# Un_RF.net
KiCad netlist of a schematic drawn in EAGLE
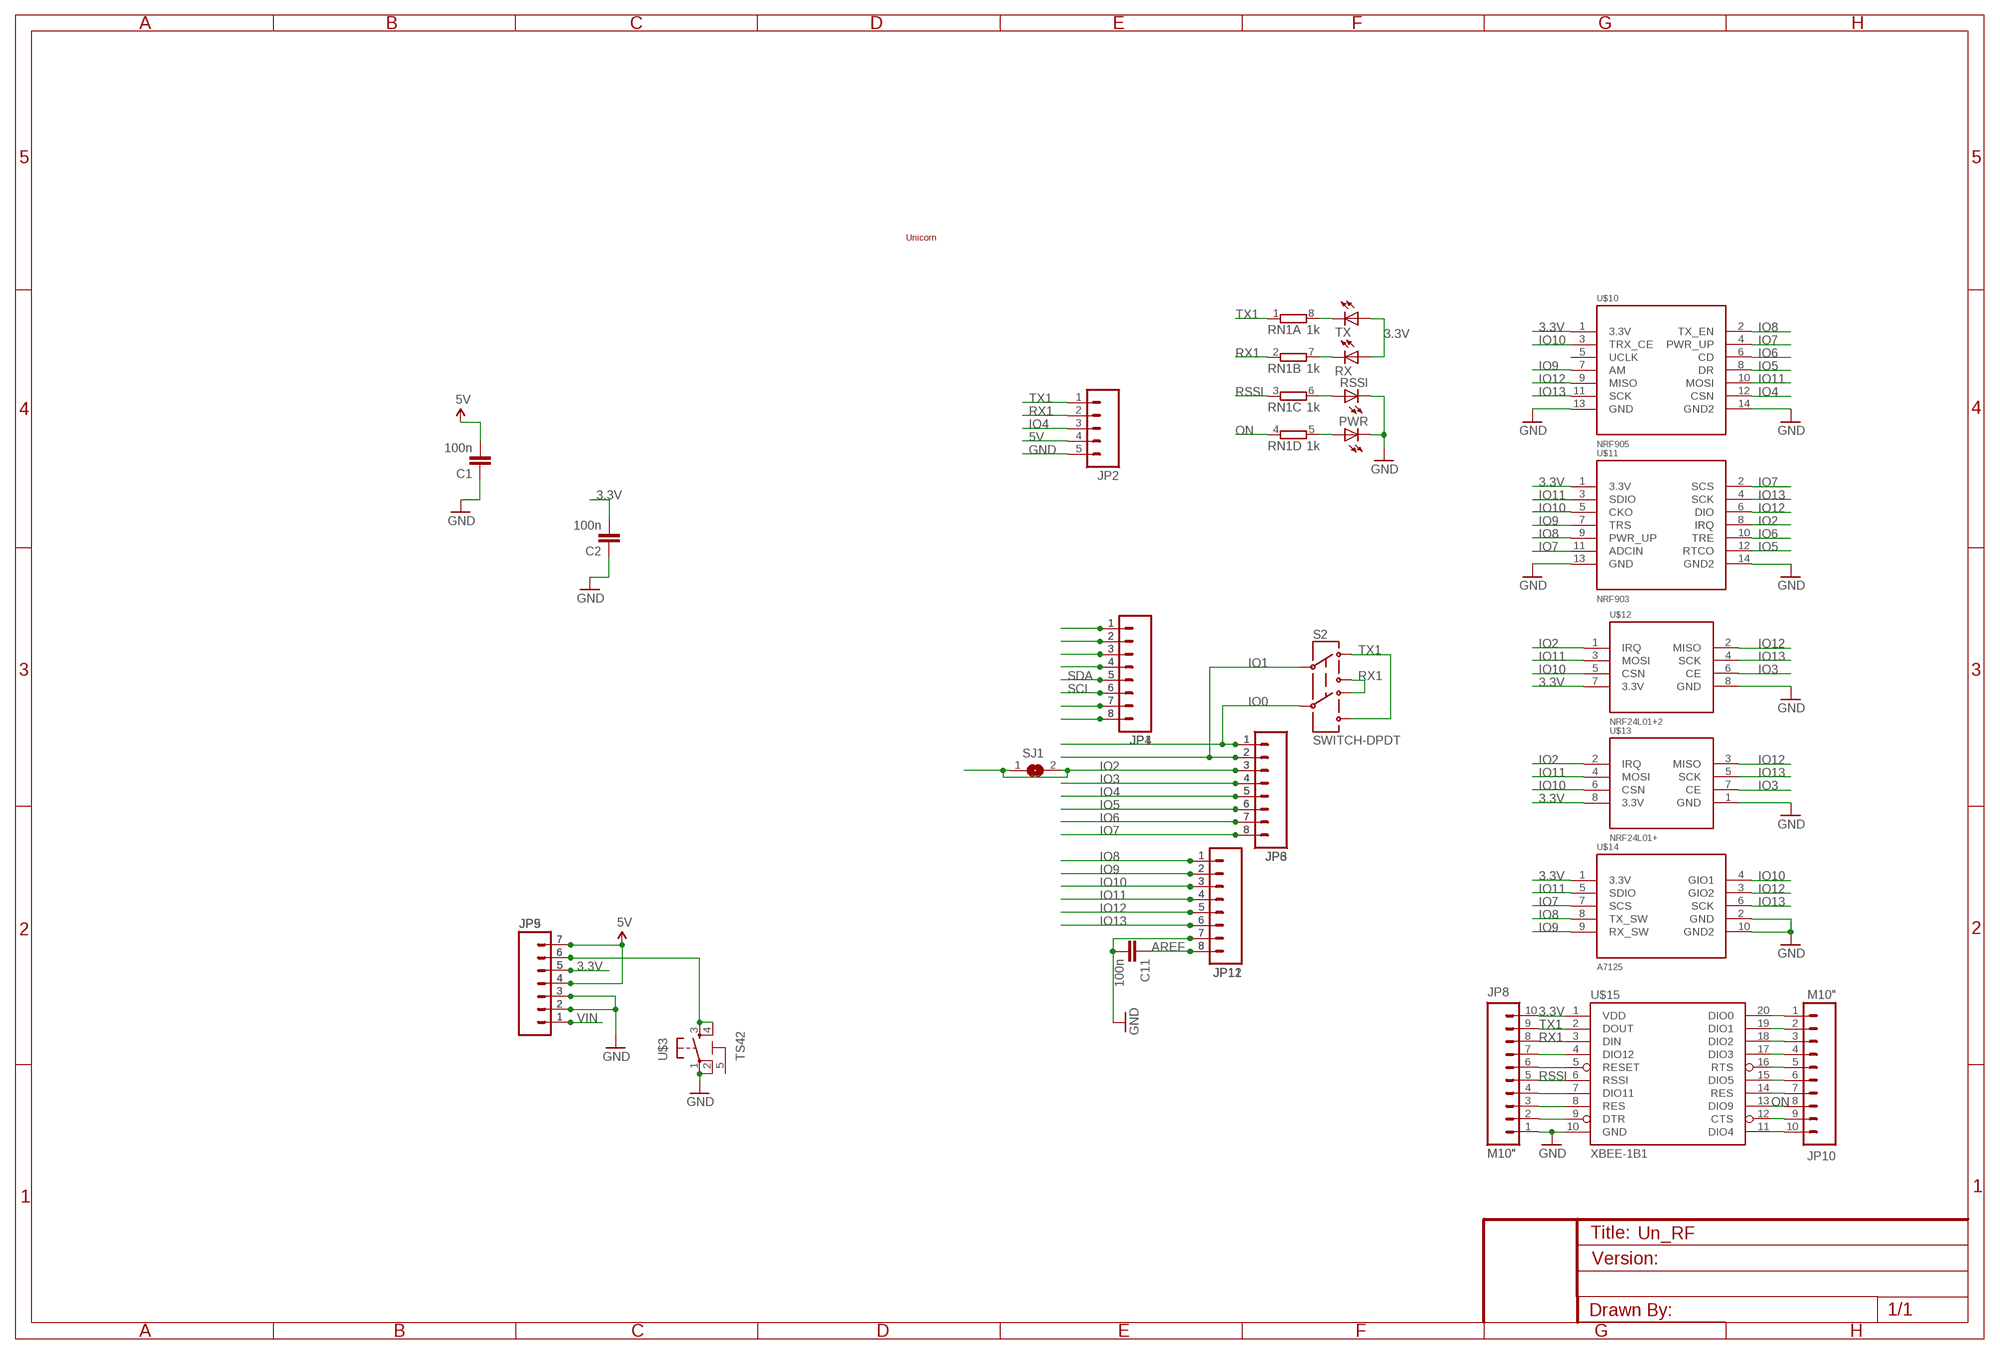
[diagram p0: schematic, sheet 1]

(export (version "E")
  (design (tool "Eeschema 10.0.6"))
  (components
    (comp (ref "C1")
      (value "100n")
      (footprint "eagle-import:0603-CAP")
      (libsource (lib "eagle-import") (part "CAP0603-CAP"))
    )
    (comp (ref "C2")
      (value "100n")
      (footprint "eagle-import:0603-CAP")
      (libsource (lib "eagle-import") (part "CAP0603-CAP"))
    )
    (comp (ref "C11")
      (value "100n")
      (footprint "eagle-import:0603-CAP")
      (libsource (lib "eagle-import") (part "CAP0603-CAP"))
    )
    (comp (ref "JP1")
      (value "M081X08")
      (footprint "eagle-import:1X08")
      (libsource (lib "eagle-import") (part "M081X08"))
    )
    (comp (ref "JP2")
      (value "M05PTH")
      (footprint "eagle-import:1X05")
      (libsource (lib "eagle-import") (part "M05PTH"))
    )
    (comp (ref "JP3")
      (value "M08")
      (footprint "eagle-import:1X08")
      (libsource (lib "eagle-import") (part "M08"))
    )
    (comp (ref "JP4")
      (value "M081X08")
      (footprint "eagle-import:1X08")
      (libsource (lib "eagle-import") (part "M081X08"))
    )
    (comp (ref "JP5")
      (value "M07")
      (footprint "eagle-import:1X07")
      (libsource (lib "eagle-import") (part "M07"))
    )
    (comp (ref "JP6")
      (value "M08")
      (footprint "eagle-import:1X08")
      (libsource (lib "eagle-import") (part "M08"))
    )
    (comp (ref "JP8")
      (value "M10\"")
      (footprint "eagle-import:1X10")
      (libsource (lib "eagle-import") (part "M10{dblquote}"))
    )
    (comp (ref "JP9")
      (value "M07")
      (footprint "eagle-import:1X07")
      (libsource (lib "eagle-import") (part "M07"))
    )
    (comp (ref "JP10")
      (value "M10\"")
      (footprint "eagle-import:1X10")
      (libsource (lib "eagle-import") (part "M10{dblquote}"))
    )
    (comp (ref "JP11")
      (value "M081X08")
      (footprint "eagle-import:1X08")
      (libsource (lib "eagle-import") (part "M081X08"))
    )
    (comp (ref "JP12")
      (value "M081X08")
      (footprint "eagle-import:1X08")
      (libsource (lib "eagle-import") (part "M081X08"))
    )
    (comp (ref "PWR")
      (value "LED0805")
      (footprint "eagle-import:LED-0805")
      (libsource (lib "eagle-import") (part "LED0805"))
    )
    (comp (ref "RN1")
      (value "1k")
      (footprint "eagle-import:CAY16")
      (libsource (lib "eagle-import") (part "4R-NCAY16"))
    )
    (comp (ref "RSSI")
      (value "LED0805")
      (footprint "eagle-import:LED-0805")
      (libsource (lib "eagle-import") (part "LED0805"))
    )
    (comp (ref "RX")
      (value "LED0805")
      (footprint "eagle-import:LED-0805")
      (libsource (lib "eagle-import") (part "LED0805"))
    )
    (comp (ref "S2")
      (value "SWITCH-DPDT")
      (footprint "eagle-import:SWITCH-P2")
      (libsource (lib "eagle-import") (part "SWITCH-DPDT"))
    )
    (comp (ref "SJ1") (value "SJ") (footprint "eagle-import:SJ") (libsource (lib "eagle-import") (part "SJ")))
    (comp (ref "TX")
      (value "LED0805")
      (footprint "eagle-import:LED-0805")
      (libsource (lib "eagle-import") (part "LED0805"))
    )
    (comp (ref "U$3")
      (value "TS42")
      (footprint "eagle-import:TS42")
      (libsource (lib "eagle-import") (part "TS42"))
    )
    (comp (ref "U$4")
      (value "UNICORN")
      (footprint "eagle-import:UNICORN_1")
      (libsource (lib "eagle-import") (part "UNICORN"))
    )
    (comp (ref "U$10")
      (value "NRF905")
      (footprint "eagle-import:2X7")
      (libsource (lib "eagle-import") (part "NRF905"))
    )
    (comp (ref "U$11")
      (value "NRF903")
      (footprint "eagle-import:2X7")
      (libsource (lib "eagle-import") (part "NRF903"))
    )
    (comp (ref "U$12")
      (value "NRF24L01+2")
      (footprint "eagle-import:2X4")
      (libsource (lib "eagle-import") (part "NRF24L01+2"))
    )
    (comp (ref "U$13")
      (value "NRF24L01+")
      (footprint "eagle-import:1X08")
      (libsource (lib "eagle-import") (part "NRF24L01+"))
    )
    (comp (ref "U$14")
      (value "A7125")
      (footprint "eagle-import:1X10-2MM")
      (libsource (lib "eagle-import") (part "A7125"))
    )
    (comp (ref "U$15")
      (value "XBEE-1B1")
      (footprint "eagle-import:XBEE-1")
      (libsource (lib "eagle-import") (part "XBEE-1B1"))
    )
  )
  (nets
    (net (code "1") (name "/3.3V") (class "Default")
      (node (ref "C2") (pin "2") (pinfunction "2_2") (pintype "passive"))
      (node (ref "JP5") (pin "5") (pinfunction "5_5") (pintype "passive"))
      (node (ref "JP8") (pin "10") (pinfunction "10_10") (pintype "passive"))
      (node (ref "JP9") (pin "5") (pinfunction "5_5") (pintype "passive"))
      (node (ref "RX") (pin "1") (pinfunction "A_1") (pintype "passive"))
      (node (ref "TX") (pin "1") (pinfunction "A_1") (pintype "passive"))
      (node (ref "U$10") (pin "1") (pinfunction "3.3V_1") (pintype "bidirectional"))
      (node (ref "U$11") (pin "1") (pinfunction "3.3V_1") (pintype "bidirectional"))
      (node (ref "U$12") (pin "7") (pinfunction "3.3V_7") (pintype "bidirectional"))
      (node (ref "U$13") (pin "8") (pinfunction "3.3V_8") (pintype "bidirectional"))
      (node (ref "U$14") (pin "1") (pinfunction "3.3V_1") (pintype "bidirectional"))
      (node (ref "U$15") (pin "1") (pinfunction "VDD_1") (pintype "power_in"))
    )
    (net (code "2") (name "/AREF") (class "Default")
      (node (ref "C11") (pin "1") (pinfunction "1_1") (pintype "passive"))
      (node (ref "JP11") (pin "8") (pinfunction "8_8") (pintype "passive"))
      (node (ref "JP12") (pin "8") (pinfunction "8_8") (pintype "passive"))
    )
    (net (code "3") (name "/IO0") (class "Default")
      (node (ref "JP3") (pin "1") (pinfunction "1_1") (pintype "passive"))
      (node (ref "JP6") (pin "1") (pinfunction "1_1") (pintype "passive"))
      (node (ref "S2") (pin "5") (pinfunction "5_5") (pintype "bidirectional"))
    )
    (net (code "4") (name "/IO1") (class "Default")
      (node (ref "JP3") (pin "2") (pinfunction "2_2") (pintype "passive"))
      (node (ref "JP6") (pin "2") (pinfunction "2_2") (pintype "passive"))
      (node (ref "S2") (pin "2") (pinfunction "2_2") (pintype "bidirectional"))
    )
    (net (code "5") (name "/IO2") (class "Default")
      (node (ref "JP3") (pin "3") (pinfunction "3_3") (pintype "passive"))
      (node (ref "JP6") (pin "3") (pinfunction "3_3") (pintype "passive"))
      (node (ref "SJ1") (pin "1") (pinfunction "1_1") (pintype "passive"))
      (node (ref "SJ1") (pin "2") (pinfunction "2_2") (pintype "passive"))
      (node (ref "U$11") (pin "8") (pinfunction "IRQ_8") (pintype "bidirectional"))
      (node (ref "U$12") (pin "1") (pinfunction "IRQ_1") (pintype "bidirectional"))
      (node (ref "U$13") (pin "2") (pinfunction "IRQ_2") (pintype "bidirectional"))
    )
    (net (code "6") (name "/IO3") (class "Default")
      (node (ref "JP3") (pin "4") (pinfunction "4_4") (pintype "passive"))
      (node (ref "JP6") (pin "4") (pinfunction "4_4") (pintype "passive"))
      (node (ref "U$12") (pin "6") (pinfunction "CE_6") (pintype "bidirectional"))
      (node (ref "U$13") (pin "7") (pinfunction "CE_7") (pintype "bidirectional"))
    )
    (net (code "7") (name "/IO4") (class "Default")
      (node (ref "JP2") (pin "3") (pinfunction "3_3") (pintype "passive"))
      (node (ref "JP3") (pin "5") (pinfunction "5_5") (pintype "passive"))
      (node (ref "JP6") (pin "5") (pinfunction "5_5") (pintype "passive"))
      (node (ref "U$10") (pin "12") (pinfunction "CSN_12") (pintype "bidirectional"))
    )
    (net (code "8") (name "/IO5") (class "Default")
      (node (ref "JP3") (pin "6") (pinfunction "6_6") (pintype "passive"))
      (node (ref "JP6") (pin "6") (pinfunction "6_6") (pintype "passive"))
      (node (ref "U$10") (pin "8") (pinfunction "DR_8") (pintype "bidirectional"))
      (node (ref "U$11") (pin "12") (pinfunction "RTCO_12") (pintype "bidirectional"))
    )
    (net (code "9") (name "/IO6") (class "Default")
      (node (ref "JP3") (pin "7") (pinfunction "7_7") (pintype "passive"))
      (node (ref "JP6") (pin "7") (pinfunction "7_7") (pintype "passive"))
      (node (ref "U$10") (pin "6") (pinfunction "CD_6") (pintype "bidirectional"))
      (node (ref "U$11") (pin "10") (pinfunction "TRE_10") (pintype "bidirectional"))
    )
    (net (code "10") (name "/IO7") (class "Default")
      (node (ref "JP3") (pin "8") (pinfunction "8_8") (pintype "passive"))
      (node (ref "JP6") (pin "8") (pinfunction "8_8") (pintype "passive"))
      (node (ref "U$10") (pin "4") (pinfunction "PWR_UP_4") (pintype "bidirectional"))
      (node (ref "U$11") (pin "11") (pinfunction "ADCIN_11") (pintype "bidirectional"))
      (node (ref "U$11") (pin "2") (pinfunction "SCS_2") (pintype "bidirectional"))
      (node (ref "U$14") (pin "7") (pinfunction "SCS_7") (pintype "bidirectional"))
    )
    (net (code "11") (name "/IO8") (class "Default")
      (node (ref "JP11") (pin "1") (pinfunction "1_1") (pintype "passive"))
      (node (ref "JP12") (pin "1") (pinfunction "1_1") (pintype "passive"))
      (node (ref "U$10") (pin "2") (pinfunction "TX_EN_2") (pintype "bidirectional"))
      (node (ref "U$11") (pin "9") (pinfunction "PWR_UP_9") (pintype "bidirectional"))
      (node (ref "U$14") (pin "8") (pinfunction "TX_SW_8") (pintype "bidirectional"))
    )
    (net (code "12") (name "/IO9") (class "Default")
      (node (ref "JP11") (pin "2") (pinfunction "2_2") (pintype "passive"))
      (node (ref "JP12") (pin "2") (pinfunction "2_2") (pintype "passive"))
      (node (ref "U$10") (pin "7") (pinfunction "AM_7") (pintype "bidirectional"))
      (node (ref "U$11") (pin "7") (pinfunction "TRS_7") (pintype "bidirectional"))
      (node (ref "U$14") (pin "9") (pinfunction "RX_SW_9") (pintype "bidirectional"))
    )
    (net (code "13") (name "/IO10") (class "Default")
      (node (ref "JP11") (pin "3") (pinfunction "3_3") (pintype "passive"))
      (node (ref "JP12") (pin "3") (pinfunction "3_3") (pintype "passive"))
      (node (ref "U$10") (pin "3") (pinfunction "TRX_CE_3") (pintype "bidirectional"))
      (node (ref "U$11") (pin "5") (pinfunction "CKO_5") (pintype "bidirectional"))
      (node (ref "U$12") (pin "5") (pinfunction "CSN_5") (pintype "bidirectional"))
      (node (ref "U$13") (pin "6") (pinfunction "CSN_6") (pintype "bidirectional"))
      (node (ref "U$14") (pin "4") (pinfunction "GIO1_4") (pintype "bidirectional"))
    )
    (net (code "14") (name "/IO11") (class "Default")
      (node (ref "JP11") (pin "4") (pinfunction "4_4") (pintype "passive"))
      (node (ref "JP12") (pin "4") (pinfunction "4_4") (pintype "passive"))
      (node (ref "U$10") (pin "10") (pinfunction "MOSI_10") (pintype "bidirectional"))
      (node (ref "U$11") (pin "3") (pinfunction "SDIO_3") (pintype "bidirectional"))
      (node (ref "U$12") (pin "3") (pinfunction "MOSI_3") (pintype "bidirectional"))
      (node (ref "U$13") (pin "4") (pinfunction "MOSI_4") (pintype "bidirectional"))
      (node (ref "U$14") (pin "5") (pinfunction "SDIO_5") (pintype "bidirectional"))
    )
    (net (code "15") (name "/IO12") (class "Default")
      (node (ref "JP11") (pin "5") (pinfunction "5_5") (pintype "passive"))
      (node (ref "JP12") (pin "5") (pinfunction "5_5") (pintype "passive"))
      (node (ref "U$10") (pin "9") (pinfunction "MISO_9") (pintype "bidirectional"))
      (node (ref "U$11") (pin "6") (pinfunction "DIO_6") (pintype "bidirectional"))
      (node (ref "U$12") (pin "2") (pinfunction "MISO_2") (pintype "bidirectional"))
      (node (ref "U$13") (pin "3") (pinfunction "MISO_3") (pintype "bidirectional"))
      (node (ref "U$14") (pin "3") (pinfunction "GIO2_3") (pintype "bidirectional"))
    )
    (net (code "16") (name "/IO13") (class "Default")
      (node (ref "JP11") (pin "6") (pinfunction "6_6") (pintype "passive"))
      (node (ref "JP12") (pin "6") (pinfunction "6_6") (pintype "passive"))
      (node (ref "U$10") (pin "11") (pinfunction "SCK_11") (pintype "bidirectional"))
      (node (ref "U$11") (pin "4") (pinfunction "SCK_4") (pintype "bidirectional"))
      (node (ref "U$12") (pin "4") (pinfunction "SCK_4") (pintype "bidirectional"))
      (node (ref "U$13") (pin "5") (pinfunction "SCK_5") (pintype "bidirectional"))
      (node (ref "U$14") (pin "6") (pinfunction "SCK_6") (pintype "bidirectional"))
    )
    (net (code "17") (name "/ON") (class "Default")
      (node (ref "JP10") (pin "8") (pinfunction "8_8") (pintype "passive"))
      (node (ref "RN1") (pin "4") (pinfunction "1_4") (pintype "passive"))
      (node (ref "U$15") (pin "13") (pinfunction "DIO9_13") (pintype "bidirectional"))
    )
    (net (code "18") (name "/RSSI") (class "Default")
      (node (ref "JP8") (pin "5") (pinfunction "5_5") (pintype "passive"))
      (node (ref "RN1") (pin "3") (pinfunction "1_3") (pintype "passive"))
      (node (ref "U$15") (pin "6") (pinfunction "RSSI_6") (pintype "bidirectional"))
    )
    (net (code "19") (name "/RX1") (class "Default")
      (node (ref "JP2") (pin "2") (pinfunction "2_2") (pintype "passive"))
      (node (ref "JP8") (pin "8") (pinfunction "8_8") (pintype "passive"))
      (node (ref "RN1") (pin "2") (pinfunction "1_2") (pintype "passive"))
      (node (ref "S2") (pin "3") (pinfunction "3_3") (pintype "bidirectional"))
      (node (ref "S2") (pin "4") (pinfunction "4_4") (pintype "bidirectional"))
      (node (ref "U$15") (pin "3") (pinfunction "DIN_3") (pintype "input"))
    )
    (net (code "20") (name "/SCL") (class "Default")
      (node (ref "JP1") (pin "6") (pinfunction "6_6") (pintype "passive"))
      (node (ref "JP4") (pin "6") (pinfunction "6_6") (pintype "passive"))
    )
    (net (code "21") (name "/SDA") (class "Default")
      (node (ref "JP1") (pin "5") (pinfunction "5_5") (pintype "passive"))
      (node (ref "JP4") (pin "5") (pinfunction "5_5") (pintype "passive"))
    )
    (net (code "22") (name "/TX1") (class "Default")
      (node (ref "JP2") (pin "1") (pinfunction "1_1") (pintype "passive"))
      (node (ref "JP8") (pin "9") (pinfunction "9_9") (pintype "passive"))
      (node (ref "RN1") (pin "1") (pinfunction "1_1") (pintype "passive"))
      (node (ref "S2") (pin "1") (pinfunction "1_1") (pintype "bidirectional"))
      (node (ref "S2") (pin "6") (pinfunction "6_6") (pintype "bidirectional"))
      (node (ref "U$15") (pin "2") (pinfunction "DOUT_2") (pintype "output"))
    )
    (net (code "23") (name "/VIN") (class "Default")
      (node (ref "JP5") (pin "1") (pinfunction "1_1") (pintype "passive"))
      (node (ref "JP9") (pin "1") (pinfunction "1_1") (pintype "passive"))
    )
    (net (code "24") (name "5V") (class "Default")
      (node (ref "C1") (pin "2") (pinfunction "2_2") (pintype "passive"))
      (node (ref "JP2") (pin "4") (pinfunction "4_4") (pintype "passive"))
      (node (ref "JP5") (pin "4") (pinfunction "4_4") (pintype "passive"))
      (node (ref "JP5") (pin "7") (pinfunction "7_7") (pintype "passive"))
      (node (ref "JP9") (pin "4") (pinfunction "4_4") (pintype "passive"))
      (node (ref "JP9") (pin "7") (pinfunction "7_7") (pintype "passive"))
    )
    (net (code "25") (name "GND") (class "Default")
      (node (ref "C1") (pin "1") (pinfunction "1_1") (pintype "passive"))
      (node (ref "C11") (pin "2") (pinfunction "2_2") (pintype "passive"))
      (node (ref "C2") (pin "1") (pinfunction "1_1") (pintype "passive"))
      (node (ref "JP11") (pin "7") (pinfunction "7_7") (pintype "passive"))
      (node (ref "JP12") (pin "7") (pinfunction "7_7") (pintype "passive"))
      (node (ref "JP2") (pin "5") (pinfunction "5_5") (pintype "passive"))
      (node (ref "JP5") (pin "2") (pinfunction "2_2") (pintype "passive"))
      (node (ref "JP5") (pin "3") (pinfunction "3_3") (pintype "passive"))
      (node (ref "JP8") (pin "1") (pinfunction "1_1") (pintype "passive"))
      (node (ref "JP9") (pin "2") (pinfunction "2_2") (pintype "passive"))
      (node (ref "JP9") (pin "3") (pinfunction "3_3") (pintype "passive"))
      (node (ref "PWR") (pin "2") (pinfunction "C_2") (pintype "passive"))
      (node (ref "RSSI") (pin "2") (pinfunction "C_2") (pintype "passive"))
      (node (ref "U$10") (pin "13") (pinfunction "GND_13") (pintype "bidirectional"))
      (node (ref "U$10") (pin "14") (pinfunction "GND2_14") (pintype "bidirectional"))
      (node (ref "U$11") (pin "13") (pinfunction "GND_13") (pintype "bidirectional"))
      (node (ref "U$11") (pin "14") (pinfunction "GND2_14") (pintype "bidirectional"))
      (node (ref "U$12") (pin "8") (pinfunction "GND_8") (pintype "bidirectional"))
      (node (ref "U$13") (pin "1") (pinfunction "GND_1") (pintype "bidirectional"))
      (node (ref "U$14") (pin "10") (pinfunction "GND2_10") (pintype "bidirectional"))
      (node (ref "U$14") (pin "2") (pinfunction "GND_2") (pintype "bidirectional"))
      (node (ref "U$15") (pin "10") (pinfunction "GND_10") (pintype "power_in"))
      (node (ref "U$3") (pin "1") (pinfunction "1_1") (pintype "passive"))
      (node (ref "U$3") (pin "2") (pinfunction "2_2") (pintype "passive"))
    )
    (net (code "26") (name "Net-(JP1-Pad1)") (class "Default")
      (node (ref "JP1") (pin "1") (pinfunction "1_1") (pintype "passive"))
      (node (ref "JP4") (pin "1") (pinfunction "1_1") (pintype "passive"))
    )
    (net (code "27") (name "Net-(JP1-Pad2)") (class "Default")
      (node (ref "JP1") (pin "2") (pinfunction "2_2") (pintype "passive"))
      (node (ref "JP4") (pin "2") (pinfunction "2_2") (pintype "passive"))
    )
    (net (code "28") (name "Net-(JP1-Pad3)") (class "Default")
      (node (ref "JP1") (pin "3") (pinfunction "3_3") (pintype "passive"))
      (node (ref "JP4") (pin "3") (pinfunction "3_3") (pintype "passive"))
    )
    (net (code "29") (name "Net-(JP1-Pad4)") (class "Default")
      (node (ref "JP1") (pin "4") (pinfunction "4_4") (pintype "passive"))
      (node (ref "JP4") (pin "4") (pinfunction "4_4") (pintype "passive"))
    )
    (net (code "30") (name "Net-(JP1-Pad7)") (class "Default")
      (node (ref "JP1") (pin "7") (pinfunction "7_7") (pintype "passive"))
      (node (ref "JP4") (pin "7") (pinfunction "7_7") (pintype "passive"))
    )
    (net (code "31") (name "Net-(JP1-Pad8)") (class "Default")
      (node (ref "JP1") (pin "8") (pinfunction "8_8") (pintype "passive"))
      (node (ref "JP4") (pin "8") (pinfunction "8_8") (pintype "passive"))
    )
    (net (code "32") (name "Net-(JP5-Pad6)") (class "Default")
      (node (ref "JP5") (pin "6") (pinfunction "6_6") (pintype "passive"))
      (node (ref "JP9") (pin "6") (pinfunction "6_6") (pintype "passive"))
      (node (ref "U$3") (pin "3") (pinfunction "3_3") (pintype "passive"))
      (node (ref "U$3") (pin "4") (pinfunction "4_4") (pintype "passive"))
    )
    (net (code "33") (name "Net-(JP8-Pad3)") (class "Default")
      (node (ref "JP8") (pin "3") (pinfunction "3_3") (pintype "passive"))
      (node (ref "U$15") (pin "8") (pinfunction "RES_8") (pintype "bidirectional"))
    )
    (net (code "34") (name "Net-(JP10-Pad7)") (class "Default")
      (node (ref "JP10") (pin "7") (pinfunction "7_7") (pintype "passive"))
      (node (ref "U$15") (pin "14") (pinfunction "RES_14") (pintype "bidirectional"))
    )
    (net (code "35") (name "Net-(PWR-A)") (class "Default")
      (node (ref "PWR") (pin "1") (pinfunction "A_1") (pintype "passive"))
      (node (ref "RN1") (pin "5") (pinfunction "2_5") (pintype "passive"))
    )
    (net (code "36") (name "Net-(RN1A-2)") (class "Default")
      (node (ref "RN1") (pin "8") (pinfunction "2_8") (pintype "passive"))
      (node (ref "TX") (pin "2") (pinfunction "C_2") (pintype "passive"))
    )
    (net (code "37") (name "Net-(RN1B-2)") (class "Default")
      (node (ref "RN1") (pin "7") (pinfunction "2_7") (pintype "passive"))
      (node (ref "RX") (pin "2") (pinfunction "C_2") (pintype "passive"))
    )
    (net (code "38") (name "Net-(RN1C-2)") (class "Default")
      (node (ref "RN1") (pin "6") (pinfunction "2_6") (pintype "passive"))
      (node (ref "RSSI") (pin "1") (pinfunction "A_1") (pintype "passive"))
    )
    (net (code "39") (name "Net-(U$15-CTS)") (class "Default")
      (node (ref "JP10") (pin "9") (pinfunction "9_9") (pintype "passive"))
      (node (ref "U$15") (pin "12") (pinfunction "CTS_12") (pintype "output"))
    )
    (net (code "40") (name "Net-(U$15-DIO0)") (class "Default")
      (node (ref "JP10") (pin "1") (pinfunction "1_1") (pintype "passive"))
      (node (ref "U$15") (pin "20") (pinfunction "DIO0_20") (pintype "bidirectional"))
    )
    (net (code "41") (name "Net-(U$15-DIO1)") (class "Default")
      (node (ref "JP10") (pin "2") (pinfunction "2_2") (pintype "passive"))
      (node (ref "U$15") (pin "19") (pinfunction "DIO1_19") (pintype "bidirectional"))
    )
    (net (code "42") (name "Net-(U$15-DIO2)") (class "Default")
      (node (ref "JP10") (pin "3") (pinfunction "3_3") (pintype "passive"))
      (node (ref "U$15") (pin "18") (pinfunction "DIO2_18") (pintype "bidirectional"))
    )
    (net (code "43") (name "Net-(U$15-DIO3)") (class "Default")
      (node (ref "JP10") (pin "4") (pinfunction "4_4") (pintype "passive"))
      (node (ref "U$15") (pin "17") (pinfunction "DIO3_17") (pintype "bidirectional"))
    )
    (net (code "44") (name "Net-(U$15-DIO4)") (class "Default")
      (node (ref "JP10") (pin "10") (pinfunction "10_10") (pintype "passive"))
      (node (ref "U$15") (pin "11") (pinfunction "DIO4_11") (pintype "bidirectional"))
    )
    (net (code "45") (name "Net-(U$15-DIO5)") (class "Default")
      (node (ref "JP10") (pin "6") (pinfunction "6_6") (pintype "passive"))
      (node (ref "U$15") (pin "15") (pinfunction "DIO5_15") (pintype "bidirectional"))
    )
    (net (code "46") (name "Net-(U$15-DIO11)") (class "Default")
      (node (ref "JP8") (pin "4") (pinfunction "4_4") (pintype "passive"))
      (node (ref "U$15") (pin "7") (pinfunction "DIO11_7") (pintype "bidirectional"))
    )
    (net (code "47") (name "Net-(U$15-DIO12)") (class "Default")
      (node (ref "JP8") (pin "7") (pinfunction "7_7") (pintype "passive"))
      (node (ref "U$15") (pin "4") (pinfunction "DIO12_4") (pintype "bidirectional"))
    )
    (net (code "48") (name "Net-(U$15-DTR)") (class "Default")
      (node (ref "JP8") (pin "2") (pinfunction "2_2") (pintype "passive"))
      (node (ref "U$15") (pin "9") (pinfunction "DTR_9") (pintype "bidirectional"))
    )
    (net (code "49") (name "Net-(U$15-RESET)") (class "Default")
      (node (ref "JP8") (pin "6") (pinfunction "6_6") (pintype "passive"))
      (node (ref "U$15") (pin "5") (pinfunction "RESET_5") (pintype "input"))
    )
    (net (code "50") (name "Net-(U$15-RTS)") (class "Default")
      (node (ref "JP10") (pin "5") (pinfunction "5_5") (pintype "passive"))
      (node (ref "U$15") (pin "16") (pinfunction "RTS_16") (pintype "input"))
    )
    (net (code "51") (name "unconnected-(U$3-Pad5)") (class "Default")
      (node (ref "U$3") (pin "5") (pinfunction "5_5") (pintype "passive"))
    )
    (net (code "52") (name "unconnected-(U$10-UCLK-Pad5)") (class "Default")
      (node (ref "U$10") (pin "5") (pinfunction "UCLK_5") (pintype "bidirectional"))
    )
  )
)
